# MAX96724_COUPON.net
KiCad netlist of a schematic drawn in Altium Designer
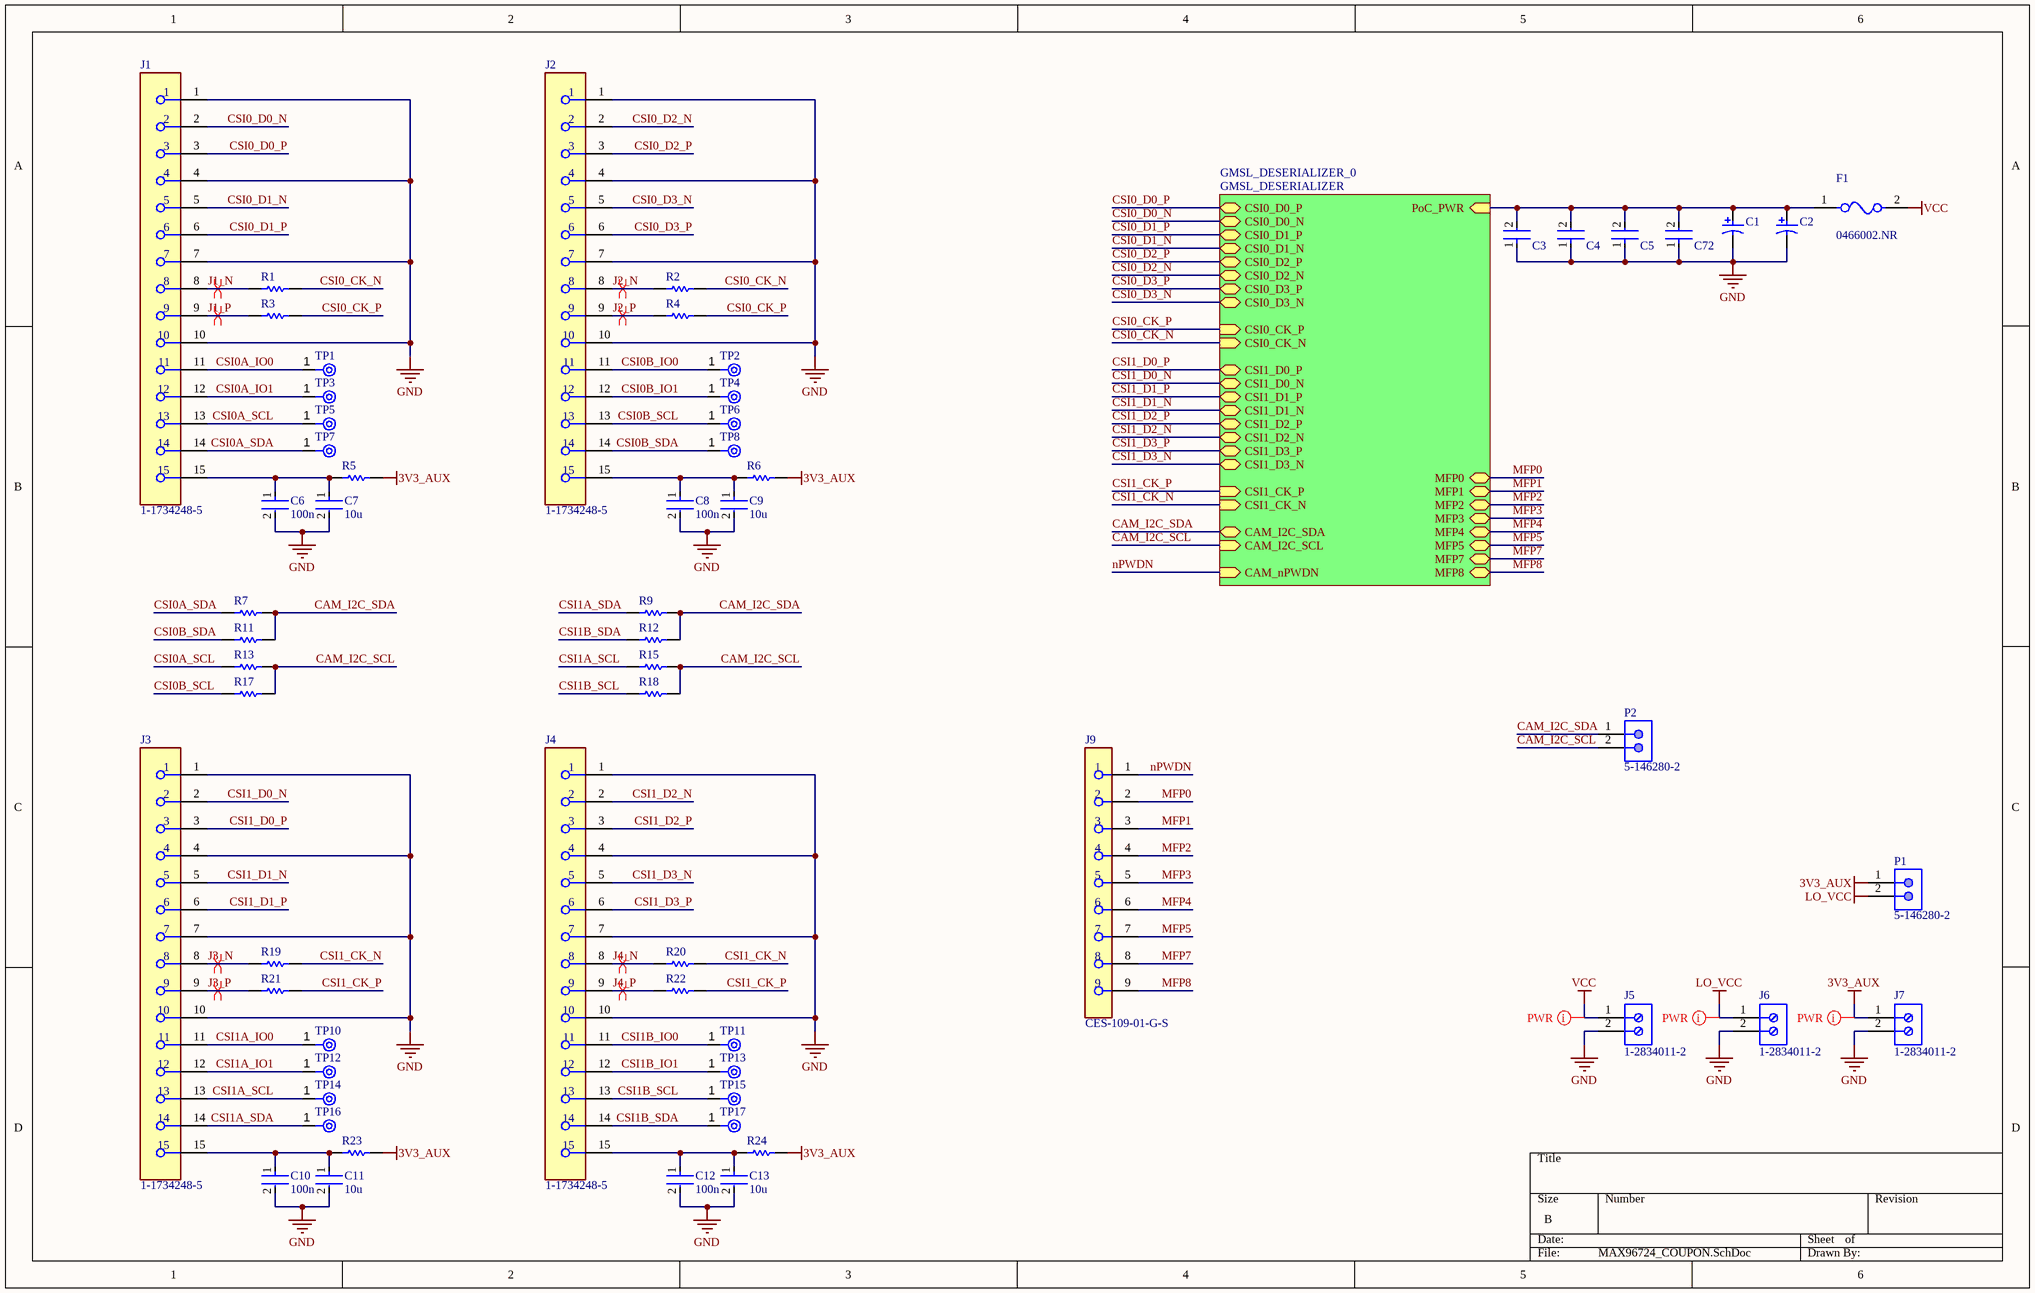
[diagram p0: MAX96724_COUPON.SchDoc]

(export (version "E")
  (design (tool "Eeschema 10.0.6"))
  (components
    (comp (ref "C1")
      (value "EEEFK1E101XP")
      (footprint "PNSC-FK-V-D8_V")
      (fields (field (name "MANUFACTURER") "Panasonic"))
      (libsource (lib "Altium Content Vault") (part "CAP-P-2"))
    )
    (comp (ref "C2")
      (value "EEEFK1E101XP")
      (footprint "PNSC-FK-V-D8_V")
      (fields (field (name "MANUFACTURER") "Panasonic"))
      (libsource (lib "Altium Content Vault") (part "CAP-P-2"))
    )
    (comp (ref "C3")
      (value "GRM21BR61E226ME44L")
      (footprint "FP-GRM21B-0_2-e0_2_0_7-IPC_B")
      (description "Chip Multilayer Ceramic Capacitors for General Purpose, 0805, 22uF, X5R, 15%, 20%, 25V")
      (fields (field (name "TOLERANCE") "20%") (field (name "VOLTAGE") "25V"))
      (libsource (lib "Altium Content Vault") (part "b4654b650e69147ec39a6b967a45e02"))
    )
    (comp (ref "C4")
      (value "GRM21BR61E226ME44L")
      (footprint "FP-GRM21B-0_2-e0_2_0_7-IPC_B")
      (description "Chip Multilayer Ceramic Capacitors for General Purpose, 0805, 22uF, X5R, 15%, 20%, 25V")
      (fields (field (name "TOLERANCE") "20%") (field (name "VOLTAGE") "25V"))
      (libsource (lib "Altium Content Vault") (part "b4654b650e69147ec39a6b967a45e02"))
    )
    (comp (ref "C5")
      (value "GRM21BR61E226ME44L")
      (footprint "FP-GRM21B-0_2-e0_2_0_7-IPC_B")
      (description "Chip Multilayer Ceramic Capacitors for General Purpose, 0805, 22uF, X5R, 15%, 20%, 25V")
      (fields (field (name "TOLERANCE") "20%") (field (name "VOLTAGE") "25V"))
      (libsource (lib "Altium Content Vault") (part "b4654b650e69147ec39a6b967a45e02"))
    )
    (comp (ref "C6")
      (value "100n")
      (footprint "FP-0402-L_1_0_0_05-W_0_5-IPC_A")
      (description "LARGE PADS, 0402 CAP, CHANGE COMMENT TO MATCH REAL P/N")
      (libsource (lib "Space Concordia") (part "b4654b650e69147ec39a6b967a45e02"))
    )
    (comp (ref "C7")
      (value "10u")
      (footprint "FP-0402-L_1_0_0_05-W_0_5-IPC_A")
      (description "LARGE PADS, 0402 CAP, CHANGE COMMENT TO MATCH REAL P/N")
      (libsource (lib "Space Concordia") (part "b4654b650e69147ec39a6b967a45e02"))
    )
    (comp (ref "C8")
      (value "100n")
      (footprint "FP-0402-L_1_0_0_05-W_0_5-IPC_A")
      (description "LARGE PADS, 0402 CAP, CHANGE COMMENT TO MATCH REAL P/N")
      (libsource (lib "Space Concordia") (part "b4654b650e69147ec39a6b967a45e02"))
    )
    (comp (ref "C9")
      (value "10u")
      (footprint "FP-0402-L_1_0_0_05-W_0_5-IPC_A")
      (description "LARGE PADS, 0402 CAP, CHANGE COMMENT TO MATCH REAL P/N")
      (libsource (lib "Space Concordia") (part "b4654b650e69147ec39a6b967a45e02"))
    )
    (comp (ref "C10")
      (value "100n")
      (footprint "FP-0402-L_1_0_0_05-W_0_5-IPC_A")
      (description "LARGE PADS, 0402 CAP, CHANGE COMMENT TO MATCH REAL P/N")
      (libsource (lib "Space Concordia") (part "b4654b650e69147ec39a6b967a45e02"))
    )
    (comp (ref "C11")
      (value "10u")
      (footprint "FP-0402-L_1_0_0_05-W_0_5-IPC_A")
      (description "LARGE PADS, 0402 CAP, CHANGE COMMENT TO MATCH REAL P/N")
      (libsource (lib "Space Concordia") (part "b4654b650e69147ec39a6b967a45e02"))
    )
    (comp (ref "C12")
      (value "100n")
      (footprint "FP-0402-L_1_0_0_05-W_0_5-IPC_A")
      (description "LARGE PADS, 0402 CAP, CHANGE COMMENT TO MATCH REAL P/N")
      (libsource (lib "Space Concordia") (part "b4654b650e69147ec39a6b967a45e02"))
    )
    (comp (ref "C13")
      (value "10u")
      (footprint "FP-0402-L_1_0_0_05-W_0_5-IPC_A")
      (description "LARGE PADS, 0402 CAP, CHANGE COMMENT TO MATCH REAL P/N")
      (libsource (lib "Space Concordia") (part "b4654b650e69147ec39a6b967a45e02"))
    )
    (comp (ref "C72")
      (value "GRM21BR61E226ME44L")
      (footprint "FP-GRM21B-0_2-e0_2_0_7-IPC_B")
      (description "Chip Multilayer Ceramic Capacitors for General Purpose, 0805, 22uF, X5R, 15%, 20%, 25V")
      (fields (field (name "TOLERANCE") "20%") (field (name "VOLTAGE") "25V"))
      (libsource (lib "Altium Content Vault") (part "b4654b650e69147ec39a6b967a45e02"))
    )
    (comp (ref "F1")
      (value "0466002.NR")
      (footprint "FP-0466-MFG")
      (description "FUSE BOARD MNT 2A 63VAC/VDC 1206")
      (fields
        (field (name "OCTOPART") "https://octopart.com/0466002.nr-littelfuse-566006")
        (field (name "MANUFACTURER") "Littelfuse")
      )
      (libsource (lib "Altium Content Vault") (part "5bcf9b9f640e542cf0359d10258e979"))
    )
    (comp (ref "J1")
      (value "1-1734248-5")
      (footprint "FP-1-1734248-5-MFG")
      (description "CONN FPC VERT 15POS 1.00MM SMD")
      (fields
        (field (name "MANUFACTURER") "TE")
        (field (name "OCTOPART") "https://octopart.com/1-1734248-5-te+connectivity-40620898")
      )
      (libsource (lib "Altium Content Vault") (part "a0777be16b290adccad2a8f9338c195"))
    )
    (comp (ref "J2")
      (value "1-1734248-5")
      (footprint "FP-1-1734248-5-MFG")
      (description "CONN FPC VERT 15POS 1.00MM SMD")
      (fields
        (field (name "MANUFACTURER") "TE")
        (field (name "OCTOPART") "https://octopart.com/1-1734248-5-te+connectivity-40620898")
      )
      (libsource (lib "Altium Content Vault") (part "a0777be16b290adccad2a8f9338c195"))
    )
    (comp (ref "J3")
      (value "1-1734248-5")
      (footprint "FP-1-1734248-5-MFG")
      (description "CONN FPC VERT 15POS 1.00MM SMD")
      (fields
        (field (name "MANUFACTURER") "TE")
        (field (name "OCTOPART") "https://octopart.com/1-1734248-5-te+connectivity-40620898")
      )
      (libsource (lib "Altium Content Vault") (part "a0777be16b290adccad2a8f9338c195"))
    )
    (comp (ref "J4")
      (value "1-1734248-5")
      (footprint "FP-1-1734248-5-MFG")
      (description "CONN FPC VERT 15POS 1.00MM SMD")
      (fields
        (field (name "MANUFACTURER") "TE")
        (field (name "OCTOPART") "https://octopart.com/1-1734248-5-te+connectivity-40620898")
      )
      (libsource (lib "Altium Content Vault") (part "a0777be16b290adccad2a8f9338c195"))
    )
    (comp (ref "J5")
      (value "1-2834011-2")
      (footprint "1-2834011-2-Footprint-1")
      (description "Barrier Strip Terminal Block")
      (libsource (lib "Space Concordia") (part "1-2834011-2"))
    )
    (comp (ref "J6")
      (value "1-2834011-2")
      (footprint "1-2834011-2-Footprint-1")
      (description "Barrier Strip Terminal Block")
      (libsource (lib "Space Concordia") (part "1-2834011-2"))
    )
    (comp (ref "J7")
      (value "1-2834011-2")
      (footprint "1-2834011-2-Footprint-1")
      (description "Barrier Strip Terminal Block")
      (libsource (lib "Space Concordia") (part "1-2834011-2"))
    )
    (comp (ref "J9")
      (value "CES-109-01-G-S")
      (footprint "FP-CES-109-01-G-S-MFG")
      (description "CES-109-01-G-S Conn Socket Strip SKT 9 POS 2.54mm Solder ST Top Entry Thru-Hole Tube")
      (libsource (lib "Altium Content Vault") (part "d3bf64047269a9dc9b641cdda8ee9d2"))
    )
    (comp (ref "P1")
      (value "5-146280-2")
      (footprint "TECO-5-146280-2_V")
      (fields (field (name "MANUFACTURER") "TE Connectivity"))
      (libsource (lib "Altium Content Vault") (part "CN-1P-M-R2"))
    )
    (comp (ref "P2")
      (value "5-146280-2")
      (footprint "TECO-5-146280-2_V")
      (fields (field (name "MANUFACTURER") "TE Connectivity"))
      (libsource (lib "Altium Content Vault") (part "CN-1P-M-R2"))
    )
    (comp (ref "R1")
      (value "0402 JUMPER")
      (footprint "RESC1005X40X25ML05T05")
      (description "READ THE NAME")
      (libsource (lib "Space Concordia") (part "CMP-009-00206-2"))
    )
    (comp (ref "R2")
      (value "0402 JUMPER")
      (footprint "RESC1005X40X25ML05T05")
      (description "READ THE NAME")
      (libsource (lib "Space Concordia") (part "CMP-009-00206-2"))
    )
    (comp (ref "R3")
      (value "0402 JUMPER")
      (footprint "RESC1005X40X25ML05T05")
      (description "READ THE NAME")
      (libsource (lib "Space Concordia") (part "CMP-009-00206-2"))
    )
    (comp (ref "R4")
      (value "0402 JUMPER")
      (footprint "RESC1005X40X25ML05T05")
      (description "READ THE NAME")
      (libsource (lib "Space Concordia") (part "CMP-009-00206-2"))
    )
    (comp (ref "R5")
      (value "RC0402JR-070RL")
      (footprint "RESC1005X40X25NL05T10")
      (fields (field (name "MANUFACTURER") "Yageo / Phycomp"))
      (libsource (lib "Altium Content Vault") (part "RES"))
    )
    (comp (ref "R6")
      (value "RC0402JR-070RL")
      (footprint "RESC1005X40X25NL05T10")
      (fields (field (name "MANUFACTURER") "Yageo / Phycomp"))
      (libsource (lib "Altium Content Vault") (part "RES"))
    )
    (comp (ref "R7")
      (value "RC0402JR-070RL")
      (footprint "RESC1005X40X25NL05T10")
      (fields (field (name "MANUFACTURER") "Yageo / Phycomp"))
      (libsource (lib "Altium Content Vault") (part "RES"))
    )
    (comp (ref "R9")
      (value "RC0402JR-070RL")
      (footprint "RESC1005X40X25NL05T10")
      (fields (field (name "MANUFACTURER") "Yageo / Phycomp"))
      (libsource (lib "Altium Content Vault") (part "RES"))
    )
    (comp (ref "R11")
      (value "RC0402JR-070RL")
      (footprint "RESC1005X40X25NL05T10")
      (fields (field (name "MANUFACTURER") "Yageo / Phycomp"))
      (libsource (lib "Altium Content Vault") (part "RES"))
    )
    (comp (ref "R12")
      (value "RC0402JR-070RL")
      (footprint "RESC1005X40X25NL05T10")
      (fields (field (name "MANUFACTURER") "Yageo / Phycomp"))
      (libsource (lib "Altium Content Vault") (part "RES"))
    )
    (comp (ref "R13")
      (value "RC0402JR-070RL")
      (footprint "RESC1005X40X25NL05T10")
      (fields (field (name "MANUFACTURER") "Yageo / Phycomp"))
      (libsource (lib "Altium Content Vault") (part "RES"))
    )
    (comp (ref "R15")
      (value "RC0402JR-070RL")
      (footprint "RESC1005X40X25NL05T10")
      (fields (field (name "MANUFACTURER") "Yageo / Phycomp"))
      (libsource (lib "Altium Content Vault") (part "RES"))
    )
    (comp (ref "R17")
      (value "RC0402JR-070RL")
      (footprint "RESC1005X40X25NL05T10")
      (fields (field (name "MANUFACTURER") "Yageo / Phycomp"))
      (libsource (lib "Altium Content Vault") (part "RES"))
    )
    (comp (ref "R18")
      (value "RC0402JR-070RL")
      (footprint "RESC1005X40X25NL05T10")
      (fields (field (name "MANUFACTURER") "Yageo / Phycomp"))
      (libsource (lib "Altium Content Vault") (part "RES"))
    )
    (comp (ref "R19")
      (value "0402 JUMPER")
      (footprint "RESC1005X40X25ML05T05")
      (description "READ THE NAME")
      (libsource (lib "Space Concordia") (part "CMP-009-00206-2"))
    )
    (comp (ref "R20")
      (value "0402 JUMPER")
      (footprint "RESC1005X40X25ML05T05")
      (description "READ THE NAME")
      (libsource (lib "Space Concordia") (part "CMP-009-00206-2"))
    )
    (comp (ref "R21")
      (value "0402 JUMPER")
      (footprint "RESC1005X40X25ML05T05")
      (description "READ THE NAME")
      (libsource (lib "Space Concordia") (part "CMP-009-00206-2"))
    )
    (comp (ref "R22")
      (value "0402 JUMPER")
      (footprint "RESC1005X40X25ML05T05")
      (description "READ THE NAME")
      (libsource (lib "Space Concordia") (part "CMP-009-00206-2"))
    )
    (comp (ref "R23")
      (value "RC0402JR-070RL")
      (footprint "RESC1005X40X25NL05T10")
      (fields (field (name "MANUFACTURER") "Yageo / Phycomp"))
      (libsource (lib "Altium Content Vault") (part "RES"))
    )
    (comp (ref "R24")
      (value "RC0402JR-070RL")
      (footprint "RESC1005X40X25NL05T10")
      (fields (field (name "MANUFACTURER") "Yageo / Phycomp"))
      (libsource (lib "Altium Content Vault") (part "RES"))
    )
    (comp (ref "TP1")
      (value "TPAD6R")
      (footprint "New footprint 1")
      (description "Test Point .6mm")
      (libsource (lib "Space Concordia") (part "TP"))
    )
    (comp (ref "TP2")
      (value "TPAD6R")
      (footprint "New footprint 1")
      (description "Test Point .6mm")
      (libsource (lib "Space Concordia") (part "TP"))
    )
    (comp (ref "TP3")
      (value "TPAD6R")
      (footprint "New footprint 1")
      (description "Test Point .6mm")
      (libsource (lib "Space Concordia") (part "TP"))
    )
    (comp (ref "TP4")
      (value "TPAD6R")
      (footprint "New footprint 1")
      (description "Test Point .6mm")
      (libsource (lib "Space Concordia") (part "TP"))
    )
    (comp (ref "TP5")
      (value "TPAD6R")
      (footprint "New footprint 1")
      (description "Test Point .6mm")
      (libsource (lib "Space Concordia") (part "TP"))
    )
    (comp (ref "TP6")
      (value "TPAD6R")
      (footprint "New footprint 1")
      (description "Test Point .6mm")
      (libsource (lib "Space Concordia") (part "TP"))
    )
    (comp (ref "TP7")
      (value "TPAD6R")
      (footprint "New footprint 1")
      (description "Test Point .6mm")
      (libsource (lib "Space Concordia") (part "TP"))
    )
    (comp (ref "TP8")
      (value "TPAD6R")
      (footprint "New footprint 1")
      (description "Test Point .6mm")
      (libsource (lib "Space Concordia") (part "TP"))
    )
    (comp (ref "TP10")
      (value "TPAD6R")
      (footprint "New footprint 1")
      (description "Test Point .6mm")
      (libsource (lib "Space Concordia") (part "TP"))
    )
    (comp (ref "TP11")
      (value "TPAD6R")
      (footprint "New footprint 1")
      (description "Test Point .6mm")
      (libsource (lib "Space Concordia") (part "TP"))
    )
    (comp (ref "TP12")
      (value "TPAD6R")
      (footprint "New footprint 1")
      (description "Test Point .6mm")
      (libsource (lib "Space Concordia") (part "TP"))
    )
    (comp (ref "TP13")
      (value "TPAD6R")
      (footprint "New footprint 1")
      (description "Test Point .6mm")
      (libsource (lib "Space Concordia") (part "TP"))
    )
    (comp (ref "TP14")
      (value "TPAD6R")
      (footprint "New footprint 1")
      (description "Test Point .6mm")
      (libsource (lib "Space Concordia") (part "TP"))
    )
    (comp (ref "TP15")
      (value "TPAD6R")
      (footprint "New footprint 1")
      (description "Test Point .6mm")
      (libsource (lib "Space Concordia") (part "TP"))
    )
    (comp (ref "TP16")
      (value "TPAD6R")
      (footprint "New footprint 1")
      (description "Test Point .6mm")
      (libsource (lib "Space Concordia") (part "TP"))
    )
    (comp (ref "TP17")
      (value "TPAD6R")
      (footprint "New footprint 1")
      (description "Test Point .6mm")
      (libsource (lib "Space Concordia") (part "TP"))
    )
  )
  (nets
    (net (code "1") (name "/CAM_I2C_SCL") (class "Default")
      (node (ref "P2") (pin "2") (pinfunction "2_2") (pintype "passive"))
      (node (ref "R13") (pin "2") (pinfunction "2_2") (pintype "passive"))
      (node (ref "R15") (pin "2") (pinfunction "2_2") (pintype "passive"))
      (node (ref "R17") (pin "2") (pinfunction "2_2") (pintype "passive"))
      (node (ref "R18") (pin "2") (pinfunction "2_2") (pintype "passive"))
    )
    (net (code "2") (name "/CAM_I2C_SDA") (class "Default")
      (node (ref "P2") (pin "1") (pinfunction "1_1") (pintype "passive"))
      (node (ref "R11") (pin "2") (pinfunction "2_2") (pintype "passive"))
      (node (ref "R12") (pin "2") (pinfunction "2_2") (pintype "passive"))
      (node (ref "R7") (pin "2") (pinfunction "2_2") (pintype "passive"))
      (node (ref "R9") (pin "2") (pinfunction "2_2") (pintype "passive"))
    )
    (net (code "3") (name "/CSI0A_IO0") (class "Default")
      (node (ref "J1") (pin "11") (pinfunction "11_11") (pintype "passive"))
      (node (ref "TP1") (pin "1") (pinfunction "TP_1") (pintype "passive"))
    )
    (net (code "4") (name "/CSI0A_IO1") (class "Default")
      (node (ref "J1") (pin "12") (pinfunction "12_12") (pintype "passive"))
      (node (ref "TP3") (pin "1") (pinfunction "TP_1") (pintype "passive"))
    )
    (net (code "5") (name "/CSI0A_SCL") (class "Default")
      (node (ref "J1") (pin "13") (pinfunction "13_13") (pintype "passive"))
      (node (ref "R13") (pin "1") (pinfunction "1_1") (pintype "passive"))
      (node (ref "TP5") (pin "1") (pinfunction "TP_1") (pintype "passive"))
    )
    (net (code "6") (name "/CSI0A_SDA") (class "Default")
      (node (ref "J1") (pin "14") (pinfunction "14_14") (pintype "passive"))
      (node (ref "R7") (pin "1") (pinfunction "1_1") (pintype "passive"))
      (node (ref "TP7") (pin "1") (pinfunction "TP_1") (pintype "passive"))
    )
    (net (code "7") (name "/CSI0B_IO0") (class "Default")
      (node (ref "J2") (pin "11") (pinfunction "11_11") (pintype "passive"))
      (node (ref "TP2") (pin "1") (pinfunction "TP_1") (pintype "passive"))
    )
    (net (code "8") (name "/CSI0B_IO1") (class "Default")
      (node (ref "J2") (pin "12") (pinfunction "12_12") (pintype "passive"))
      (node (ref "TP4") (pin "1") (pinfunction "TP_1") (pintype "passive"))
    )
    (net (code "9") (name "/CSI0B_SCL") (class "Default")
      (node (ref "J2") (pin "13") (pinfunction "13_13") (pintype "passive"))
      (node (ref "R17") (pin "1") (pinfunction "1_1") (pintype "passive"))
      (node (ref "TP6") (pin "1") (pinfunction "TP_1") (pintype "passive"))
    )
    (net (code "10") (name "/CSI0B_SDA") (class "Default")
      (node (ref "J2") (pin "14") (pinfunction "14_14") (pintype "passive"))
      (node (ref "R11") (pin "1") (pinfunction "1_1") (pintype "passive"))
      (node (ref "TP8") (pin "1") (pinfunction "TP_1") (pintype "passive"))
    )
    (net (code "11") (name "/CSI0_CK_N") (class "Default")
      (node (ref "R1") (pin "2") (pinfunction "2_2") (pintype "passive"))
      (node (ref "R2") (pin "2") (pinfunction "2_2") (pintype "passive"))
    )
    (net (code "12") (name "/CSI0_CK_P") (class "Default")
      (node (ref "R3") (pin "2") (pinfunction "2_2") (pintype "passive"))
      (node (ref "R4") (pin "2") (pinfunction "2_2") (pintype "passive"))
    )
    (net (code "13") (name "/CSI0_D0_N") (class "Default")
      (node (ref "J1") (pin "2") (pinfunction "2_2") (pintype "passive"))
    )
    (net (code "14") (name "/CSI0_D0_P") (class "Default")
      (node (ref "J1") (pin "3") (pinfunction "3_3") (pintype "passive"))
    )
    (net (code "15") (name "/CSI0_D1_N") (class "Default")
      (node (ref "J1") (pin "5") (pinfunction "5_5") (pintype "passive"))
    )
    (net (code "16") (name "/CSI0_D1_P") (class "Default")
      (node (ref "J1") (pin "6") (pinfunction "6_6") (pintype "passive"))
    )
    (net (code "17") (name "/CSI0_D2_N") (class "Default")
      (node (ref "J2") (pin "2") (pinfunction "2_2") (pintype "passive"))
    )
    (net (code "18") (name "/CSI0_D2_P") (class "Default")
      (node (ref "J2") (pin "3") (pinfunction "3_3") (pintype "passive"))
    )
    (net (code "19") (name "/CSI0_D3_N") (class "Default")
      (node (ref "J2") (pin "5") (pinfunction "5_5") (pintype "passive"))
    )
    (net (code "20") (name "/CSI0_D3_P") (class "Default")
      (node (ref "J2") (pin "6") (pinfunction "6_6") (pintype "passive"))
    )
    (net (code "21") (name "/CSI1A_IO0") (class "Default")
      (node (ref "J3") (pin "11") (pinfunction "11_11") (pintype "passive"))
      (node (ref "TP10") (pin "1") (pinfunction "TP_1") (pintype "passive"))
    )
    (net (code "22") (name "/CSI1A_IO1") (class "Default")
      (node (ref "J3") (pin "12") (pinfunction "12_12") (pintype "passive"))
      (node (ref "TP12") (pin "1") (pinfunction "TP_1") (pintype "passive"))
    )
    (net (code "23") (name "/CSI1A_SCL") (class "Default")
      (node (ref "J3") (pin "13") (pinfunction "13_13") (pintype "passive"))
      (node (ref "R15") (pin "1") (pinfunction "1_1") (pintype "passive"))
      (node (ref "TP14") (pin "1") (pinfunction "TP_1") (pintype "passive"))
    )
    (net (code "24") (name "/CSI1A_SDA") (class "Default")
      (node (ref "J3") (pin "14") (pinfunction "14_14") (pintype "passive"))
      (node (ref "R9") (pin "1") (pinfunction "1_1") (pintype "passive"))
      (node (ref "TP16") (pin "1") (pinfunction "TP_1") (pintype "passive"))
    )
    (net (code "25") (name "/CSI1B_IO0") (class "Default")
      (node (ref "J4") (pin "11") (pinfunction "11_11") (pintype "passive"))
      (node (ref "TP11") (pin "1") (pinfunction "TP_1") (pintype "passive"))
    )
    (net (code "26") (name "/CSI1B_IO1") (class "Default")
      (node (ref "J4") (pin "12") (pinfunction "12_12") (pintype "passive"))
      (node (ref "TP13") (pin "1") (pinfunction "TP_1") (pintype "passive"))
    )
    (net (code "27") (name "/CSI1B_SCL") (class "Default")
      (node (ref "J4") (pin "13") (pinfunction "13_13") (pintype "passive"))
      (node (ref "R18") (pin "1") (pinfunction "1_1") (pintype "passive"))
      (node (ref "TP15") (pin "1") (pinfunction "TP_1") (pintype "passive"))
    )
    (net (code "28") (name "/CSI1B_SDA") (class "Default")
      (node (ref "J4") (pin "14") (pinfunction "14_14") (pintype "passive"))
      (node (ref "R12") (pin "1") (pinfunction "1_1") (pintype "passive"))
      (node (ref "TP17") (pin "1") (pinfunction "TP_1") (pintype "passive"))
    )
    (net (code "29") (name "/CSI1_CK_N") (class "Default")
      (node (ref "R19") (pin "2") (pinfunction "2_2") (pintype "passive"))
      (node (ref "R20") (pin "2") (pinfunction "2_2") (pintype "passive"))
    )
    (net (code "30") (name "/CSI1_CK_P") (class "Default")
      (node (ref "R21") (pin "2") (pinfunction "2_2") (pintype "passive"))
      (node (ref "R22") (pin "2") (pinfunction "2_2") (pintype "passive"))
    )
    (net (code "31") (name "/CSI1_D0_N") (class "Default")
      (node (ref "J3") (pin "2") (pinfunction "2_2") (pintype "passive"))
    )
    (net (code "32") (name "/CSI1_D0_P") (class "Default")
      (node (ref "J3") (pin "3") (pinfunction "3_3") (pintype "passive"))
    )
    (net (code "33") (name "/CSI1_D1_N") (class "Default")
      (node (ref "J3") (pin "5") (pinfunction "5_5") (pintype "passive"))
    )
    (net (code "34") (name "/CSI1_D1_P") (class "Default")
      (node (ref "J3") (pin "6") (pinfunction "6_6") (pintype "passive"))
    )
    (net (code "35") (name "/CSI1_D2_N") (class "Default")
      (node (ref "J4") (pin "2") (pinfunction "2_2") (pintype "passive"))
    )
    (net (code "36") (name "/CSI1_D2_P") (class "Default")
      (node (ref "J4") (pin "3") (pinfunction "3_3") (pintype "passive"))
    )
    (net (code "37") (name "/CSI1_D3_N") (class "Default")
      (node (ref "J4") (pin "5") (pinfunction "5_5") (pintype "passive"))
    )
    (net (code "38") (name "/CSI1_D3_P") (class "Default")
      (node (ref "J4") (pin "6") (pinfunction "6_6") (pintype "passive"))
    )
    (net (code "39") (name "/J1_N") (class "Default")
      (node (ref "J1") (pin "8") (pinfunction "8_8") (pintype "passive"))
      (node (ref "R1") (pin "1") (pinfunction "1_1") (pintype "passive"))
    )
    (net (code "40") (name "/J1_P") (class "Default")
      (node (ref "J1") (pin "9") (pinfunction "9_9") (pintype "passive"))
      (node (ref "R3") (pin "1") (pinfunction "1_1") (pintype "passive"))
    )
    (net (code "41") (name "/J2_N") (class "Default")
      (node (ref "J2") (pin "8") (pinfunction "8_8") (pintype "passive"))
      (node (ref "R2") (pin "1") (pinfunction "1_1") (pintype "passive"))
    )
    (net (code "42") (name "/J2_P") (class "Default")
      (node (ref "J2") (pin "9") (pinfunction "9_9") (pintype "passive"))
      (node (ref "R4") (pin "1") (pinfunction "1_1") (pintype "passive"))
    )
    (net (code "43") (name "/J3_N") (class "Default")
      (node (ref "J3") (pin "8") (pinfunction "8_8") (pintype "passive"))
      (node (ref "R19") (pin "1") (pinfunction "1_1") (pintype "passive"))
    )
    (net (code "44") (name "/J3_P") (class "Default")
      (node (ref "J3") (pin "9") (pinfunction "9_9") (pintype "passive"))
      (node (ref "R21") (pin "1") (pinfunction "1_1") (pintype "passive"))
    )
    (net (code "45") (name "/J4_N") (class "Default")
      (node (ref "J4") (pin "8") (pinfunction "8_8") (pintype "passive"))
      (node (ref "R20") (pin "1") (pinfunction "1_1") (pintype "passive"))
    )
    (net (code "46") (name "/J4_P") (class "Default")
      (node (ref "J4") (pin "9") (pinfunction "9_9") (pintype "passive"))
      (node (ref "R22") (pin "1") (pinfunction "1_1") (pintype "passive"))
    )
    (net (code "47") (name "/MFP0") (class "Default")
      (node (ref "J9") (pin "2") (pinfunction "2_2") (pintype "passive"))
    )
    (net (code "48") (name "/MFP1") (class "Default")
      (node (ref "J9") (pin "3") (pinfunction "3_3") (pintype "passive"))
    )
    (net (code "49") (name "/MFP2") (class "Default")
      (node (ref "J9") (pin "4") (pinfunction "4_4") (pintype "passive"))
    )
    (net (code "50") (name "/MFP3") (class "Default")
      (node (ref "J9") (pin "5") (pinfunction "5_5") (pintype "passive"))
    )
    (net (code "51") (name "/MFP4") (class "Default")
      (node (ref "J9") (pin "6") (pinfunction "6_6") (pintype "passive"))
    )
    (net (code "52") (name "/MFP5") (class "Default")
      (node (ref "J9") (pin "7") (pinfunction "7_7") (pintype "passive"))
    )
    (net (code "53") (name "/MFP7") (class "Default")
      (node (ref "J9") (pin "8") (pinfunction "8_8") (pintype "passive"))
    )
    (net (code "54") (name "/MFP8") (class "Default")
      (node (ref "J9") (pin "9") (pinfunction "9_9") (pintype "passive"))
    )
    (net (code "55") (name "/PoC_PWR") (class "Default")
      (node (ref "C1") (pin "1") (pinfunction "1_1") (pintype "passive"))
      (node (ref "C2") (pin "1") (pinfunction "1_1") (pintype "passive"))
      (node (ref "C3") (pin "2") (pinfunction "2_2") (pintype "passive"))
      (node (ref "C4") (pin "2") (pinfunction "2_2") (pintype "passive"))
      (node (ref "C5") (pin "2") (pinfunction "2_2") (pintype "passive"))
      (node (ref "C72") (pin "2") (pinfunction "2_2") (pintype "passive"))
      (node (ref "F1") (pin "1") (pinfunction "1_1") (pintype "passive"))
    )
    (net (code "56") (name "/nPWDN") (class "Default")
      (node (ref "J9") (pin "1") (pinfunction "1_1") (pintype "passive"))
    )
    (net (code "57") (name "3V3_AUX") (class "Default")
      (node (ref "J7") (pin "1") (pinfunction "1_1") (pintype "passive"))
      (node (ref "P1") (pin "1") (pinfunction "1_1") (pintype "passive"))
      (node (ref "R23") (pin "2") (pinfunction "2_2") (pintype "passive"))
      (node (ref "R24") (pin "2") (pinfunction "2_2") (pintype "passive"))
      (node (ref "R5") (pin "2") (pinfunction "2_2") (pintype "passive"))
      (node (ref "R6") (pin "2") (pinfunction "2_2") (pintype "passive"))
    )
    (net (code "58") (name "GND") (class "Default")
      (node (ref "C1") (pin "2") (pinfunction "2_2") (pintype "passive"))
      (node (ref "C10") (pin "2") (pinfunction "2_2") (pintype "passive"))
      (node (ref "C11") (pin "2") (pinfunction "2_2") (pintype "passive"))
      (node (ref "C12") (pin "2") (pinfunction "2_2") (pintype "passive"))
      (node (ref "C13") (pin "2") (pinfunction "2_2") (pintype "passive"))
      (node (ref "C2") (pin "2") (pinfunction "2_2") (pintype "passive"))
      (node (ref "C3") (pin "1") (pinfunction "1_1") (pintype "passive"))
      (node (ref "C4") (pin "1") (pinfunction "1_1") (pintype "passive"))
      (node (ref "C5") (pin "1") (pinfunction "1_1") (pintype "passive"))
      (node (ref "C6") (pin "2") (pinfunction "2_2") (pintype "passive"))
      (node (ref "C7") (pin "2") (pinfunction "2_2") (pintype "passive"))
      (node (ref "C72") (pin "1") (pinfunction "1_1") (pintype "passive"))
      (node (ref "C8") (pin "2") (pinfunction "2_2") (pintype "passive"))
      (node (ref "C9") (pin "2") (pinfunction "2_2") (pintype "passive"))
      (node (ref "J1") (pin "1") (pinfunction "1_1") (pintype "passive"))
      (node (ref "J1") (pin "10") (pinfunction "10_10") (pintype "passive"))
      (node (ref "J1") (pin "4") (pinfunction "4_4") (pintype "passive"))
      (node (ref "J1") (pin "7") (pinfunction "7_7") (pintype "passive"))
      (node (ref "J2") (pin "1") (pinfunction "1_1") (pintype "passive"))
      (node (ref "J2") (pin "10") (pinfunction "10_10") (pintype "passive"))
      (node (ref "J2") (pin "4") (pinfunction "4_4") (pintype "passive"))
      (node (ref "J2") (pin "7") (pinfunction "7_7") (pintype "passive"))
      (node (ref "J3") (pin "1") (pinfunction "1_1") (pintype "passive"))
      (node (ref "J3") (pin "10") (pinfunction "10_10") (pintype "passive"))
      (node (ref "J3") (pin "4") (pinfunction "4_4") (pintype "passive"))
      (node (ref "J3") (pin "7") (pinfunction "7_7") (pintype "passive"))
      (node (ref "J4") (pin "1") (pinfunction "1_1") (pintype "passive"))
      (node (ref "J4") (pin "10") (pinfunction "10_10") (pintype "passive"))
      (node (ref "J4") (pin "4") (pinfunction "4_4") (pintype "passive"))
      (node (ref "J4") (pin "7") (pinfunction "7_7") (pintype "passive"))
      (node (ref "J5") (pin "2") (pinfunction "2_2") (pintype "passive"))
      (node (ref "J6") (pin "2") (pinfunction "2_2") (pintype "passive"))
      (node (ref "J7") (pin "2") (pinfunction "2_2") (pintype "passive"))
    )
    (net (code "59") (name "LO_VCC") (class "Default")
      (node (ref "J6") (pin "1") (pinfunction "1_1") (pintype "passive"))
      (node (ref "P1") (pin "2") (pinfunction "2_2") (pintype "passive"))
    )
    (net (code "60") (name "Net-(C6-Pad1)") (class "Default")
      (node (ref "C6") (pin "1") (pinfunction "1_1") (pintype "passive"))
      (node (ref "C7") (pin "1") (pinfunction "1_1") (pintype "passive"))
      (node (ref "J1") (pin "15") (pinfunction "15_15") (pintype "passive"))
      (node (ref "R5") (pin "1") (pinfunction "1_1") (pintype "passive"))
    )
    (net (code "61") (name "Net-(C8-Pad1)") (class "Default")
      (node (ref "C8") (pin "1") (pinfunction "1_1") (pintype "passive"))
      (node (ref "C9") (pin "1") (pinfunction "1_1") (pintype "passive"))
      (node (ref "J2") (pin "15") (pinfunction "15_15") (pintype "passive"))
      (node (ref "R6") (pin "1") (pinfunction "1_1") (pintype "passive"))
    )
    (net (code "62") (name "Net-(C10-Pad1)") (class "Default")
      (node (ref "C10") (pin "1") (pinfunction "1_1") (pintype "passive"))
      (node (ref "C11") (pin "1") (pinfunction "1_1") (pintype "passive"))
      (node (ref "J3") (pin "15") (pinfunction "15_15") (pintype "passive"))
      (node (ref "R23") (pin "1") (pinfunction "1_1") (pintype "passive"))
    )
    (net (code "63") (name "Net-(C12-Pad1)") (class "Default")
      (node (ref "C12") (pin "1") (pinfunction "1_1") (pintype "passive"))
      (node (ref "C13") (pin "1") (pinfunction "1_1") (pintype "passive"))
      (node (ref "J4") (pin "15") (pinfunction "15_15") (pintype "passive"))
      (node (ref "R24") (pin "1") (pinfunction "1_1") (pintype "passive"))
    )
    (net (code "64") (name "VCC") (class "Default")
      (node (ref "F1") (pin "2") (pinfunction "2_2") (pintype "passive"))
      (node (ref "J5") (pin "1") (pinfunction "1_1") (pintype "passive"))
    )
  )
)
